# MCU.net
KiCad netlist of a schematic drawn in Altium Designer
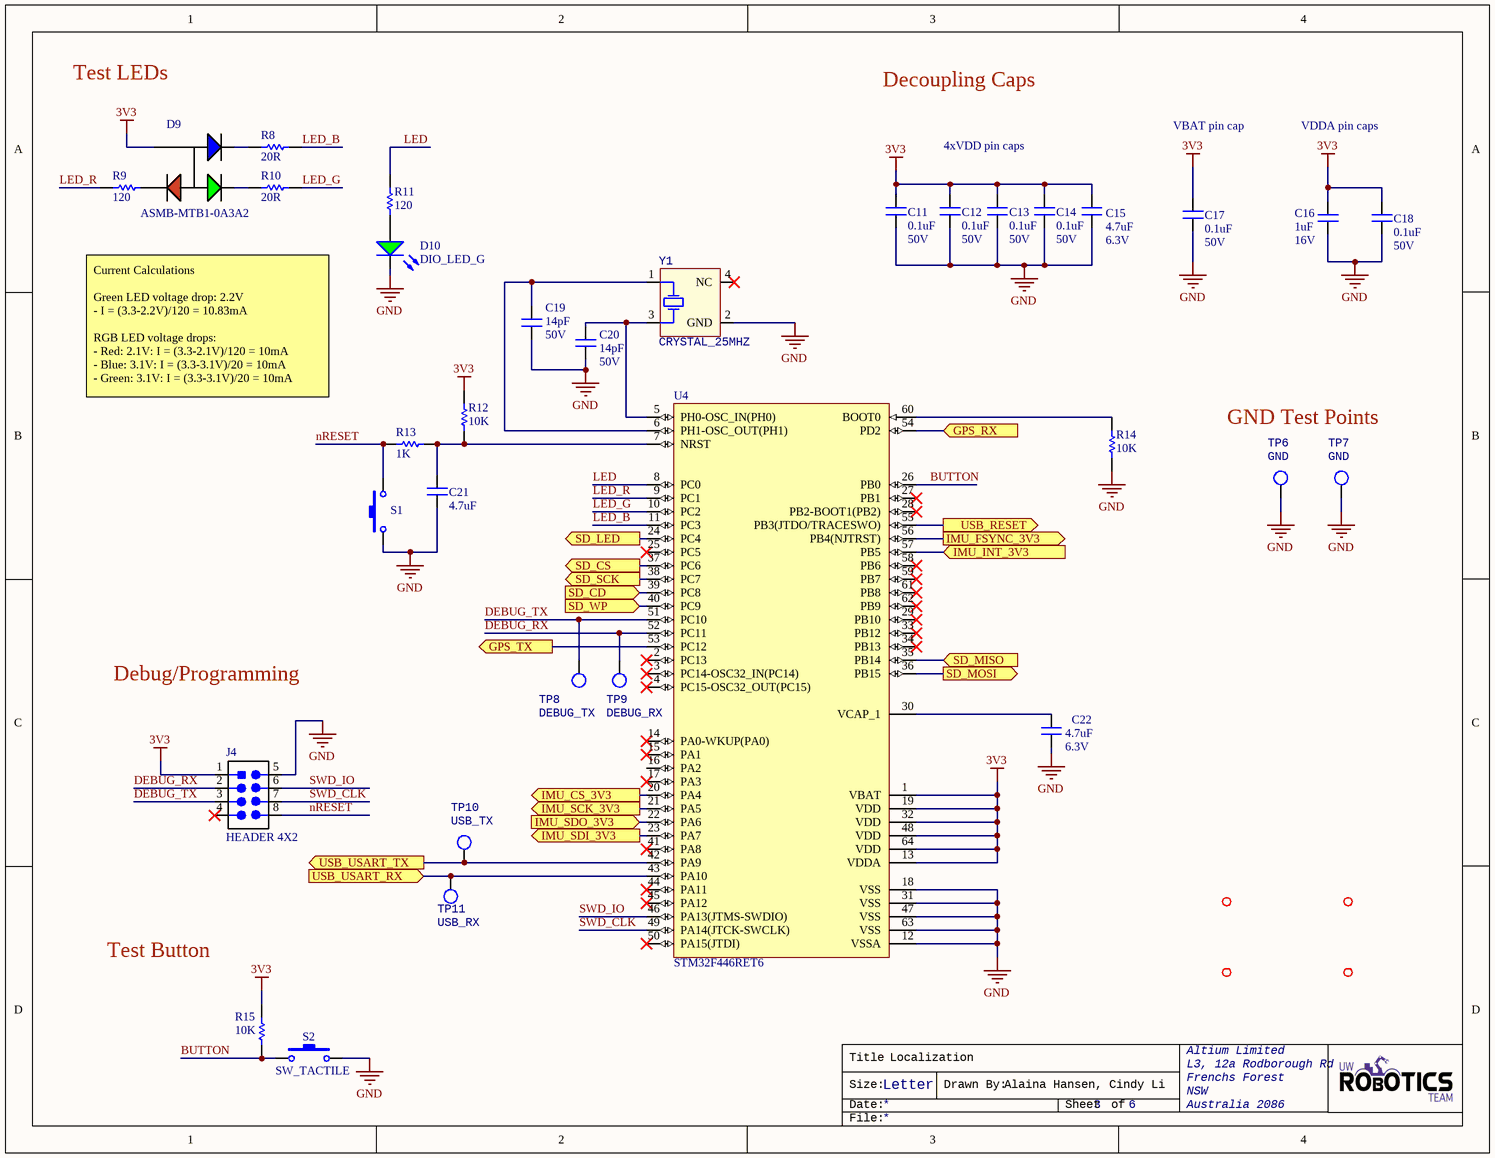
[diagram p0: MCU.SchDoc]

(export (version "E")
  (design (tool "Eeschema 10.0.6"))
  (components
    (comp (ref "C11")
      (value "0.1uF")
      (footprint "CAPC2012X140N")
      (description "CAP CER 0.1UF 50V X7R 0805")
      (fields
        (field (name "TOLERANCE") "10%")
        (field (name "VOLTAGE RATING") "50V")
        (field (name "Comment") "CAP_0.1uF_50V_0805")
      )
      (libsource (lib "UWRT_Schematic_Library_2020") (part "CAP_0.1uF_50V_0805"))
    )
    (comp (ref "C12")
      (value "0.1uF")
      (footprint "CAPC2012X140N")
      (description "CAP CER 0.1UF 50V X7R 0805")
      (fields
        (field (name "TOLERANCE") "10%")
        (field (name "VOLTAGE RATING") "50V")
        (field (name "Comment") "CAP_0.1uF_50V_0805")
      )
      (libsource (lib "UWRT_Schematic_Library_2020") (part "CAP_0.1uF_50V_0805"))
    )
    (comp (ref "C13")
      (value "0.1uF")
      (footprint "CAPC2012X140N")
      (description "CAP CER 0.1UF 50V X7R 0805")
      (fields
        (field (name "TOLERANCE") "10%")
        (field (name "VOLTAGE RATING") "50V")
        (field (name "Comment") "CAP_0.1uF_50V_0805")
      )
      (libsource (lib "UWRT_Schematic_Library_2020") (part "CAP_0.1uF_50V_0805"))
    )
    (comp (ref "C14")
      (value "0.1uF")
      (footprint "CAPC2012X140N")
      (description "CAP CER 0.1UF 50V X7R 0805")
      (fields
        (field (name "TOLERANCE") "10%")
        (field (name "VOLTAGE RATING") "50V")
        (field (name "Comment") "CAP_0.1uF_50V_0805")
      )
      (libsource (lib "UWRT_Schematic_Library_2020") (part "CAP_0.1uF_50V_0805"))
    )
    (comp (ref "C15")
      (value "4.7uF")
      (footprint "CAPC0603(1608)55_N")
      (description "CAP CER 4.7UF 6.3V X5R 0603")
      (fields (field (name "VOLTAGE RATING") "6.3V") (field (name "Comment") "CAP_4.7uF_0603"))
      (libsource (lib "UWRT_Schematic_Library_2020") (part "CAP_4.7uF_0603"))
    )
    (comp (ref "C16")
      (value "1uF")
      (footprint "CAPC0603(1608)55_N")
      (description "CAP CER 1UF 16V Y5V 0603")
      (fields
        (field (name "VOLTAGE RATING") "16V")
        (field (name "MANUFACTURER PART NUMBER") "CC0603ZRY5V7BB105")
        (field (name "Comment") "CAP_1uF_16V_0603")
      )
      (libsource (lib "UWRT_Schematic_Library_2020") (part "CAP_1uF_16V_0603"))
    )
    (comp (ref "C17")
      (value "0.1uF")
      (footprint "CAPC2012X140N")
      (description "CAP CER 0.1UF 50V X7R 0805")
      (fields
        (field (name "TOLERANCE") "10%")
        (field (name "VOLTAGE RATING") "50V")
        (field (name "Comment") "CAP_0.1uF_50V_0805")
      )
      (libsource (lib "UWRT_Schematic_Library_2020") (part "CAP_0.1uF_50V_0805"))
    )
    (comp (ref "C18")
      (value "0.1uF")
      (footprint "CAPC2012X140N")
      (description "CAP CER 0.1UF 50V X7R 0805")
      (fields
        (field (name "TOLERANCE") "10%")
        (field (name "VOLTAGE RATING") "50V")
        (field (name "Comment") "CAP_0.1uF_50V_0805")
      )
      (libsource (lib "UWRT_Schematic_Library_2020") (part "CAP_0.1uF_50V_0805"))
    )
    (comp (ref "C19")
      (value "14pF")
      (footprint "CAPC0603(1608)55_N")
      (description "Cap Ceramic 14pF 50V C0G 5% SMD 0603 125C Cardboard T/R")
      (fields
        (field (name "TOLERANCE") "5%")
        (field (name "VOLTAGE RATING (DC)") "50V")
        (field (name "Comment") "CL10C140JB8NNNC")
      )
      (libsource (lib "UWRT_Schematic_Library_2020") (part "CL10C140JB8NNNC"))
    )
    (comp (ref "C20")
      (value "14pF")
      (footprint "CAPC0603(1608)55_N")
      (description "Cap Ceramic 14pF 50V C0G 5% SMD 0603 125C Cardboard T/R")
      (fields
        (field (name "TOLERANCE") "5%")
        (field (name "VOLTAGE RATING (DC)") "50V")
        (field (name "Comment") "CL10C140JB8NNNC")
      )
      (libsource (lib "UWRT_Schematic_Library_2020") (part "CL10C140JB8NNNC"))
    )
    (comp (ref "C21")
      (value "4.7uF")
      (footprint "CAPC0603(1608)55_N")
      (description "CAP CER 4.7UF 6.3V X5R 0603")
      (fields (field (name "Comment") "CAP_4.7uF_0603"))
      (libsource (lib "UWRT_Schematic_Library_2020") (part "CAP_4.7uF_0603"))
    )
    (comp (ref "C22")
      (value "4.7uF")
      (footprint "CAPC0603(1608)55_N")
      (description "CAP CER 4.7UF 6.3V X5R 0603")
      (fields (field (name "VOLTAGE RATING") "6.3V") (field (name "Comment") "CAP_4.7uF_0603"))
      (libsource (lib "UWRT_Schematic_Library_2020") (part "CAP_4.7uF_0603"))
    )
    (comp (ref "D9")
      (value "LED_RGB")
      (footprint "LED_RGB")
      (description "LED RGB DIFFUSED 4PLCC SMD")
      (fields (field (name "MANUFACTURER PART NUMBER 1") "ASMB-MTB1-0A3A2"))
      (libsource (lib "UWRT_Schematic_Library_2020") (part "LED_RGB"))
    )
    (comp (ref "D10")
      (value "DIO_LED_G")
      (footprint "LED_0805_LINE")
      (description "LED GREEN DIFFUSED 0805 SMD")
      (libsource (lib "UWRT_Schematic_Library_2020") (part "DIO_LED_G"))
    )
    (comp (ref "J4")
      (value "HEADER 4X2")
      (footprint "UWRT_Footprint_Library_2020:HEADER_2X4")
      (description "CONN HEADER VERT 8POS 2.54MM")
      (libsource (lib "UWRT_Schematic_Library_2020") (part "HEADER 4X2"))
    )
    (comp (ref "MH1")
      (value "MOUNTING_HOLES")
      (footprint "MOUNTING_HOLE")
      (description "6cm x 6cm")
      (libsource (lib "UWRT_Schematic_Library_2020") (part "MOUNTING_HOLES"))
    )
    (comp (ref "MH2")
      (value "MOUNTING_HOLES")
      (footprint "MOUNTING_HOLE")
      (description "6cm x 6cm")
      (libsource (lib "UWRT_Schematic_Library_2020") (part "MOUNTING_HOLES"))
    )
    (comp (ref "MH3")
      (value "MOUNTING_HOLES")
      (footprint "MOUNTING_HOLE")
      (description "6cm x 6cm")
      (libsource (lib "UWRT_Schematic_Library_2020") (part "MOUNTING_HOLES"))
    )
    (comp (ref "MH4")
      (value "MOUNTING_HOLES")
      (footprint "MOUNTING_HOLE")
      (description "6cm x 6cm")
      (libsource (lib "UWRT_Schematic_Library_2020") (part "MOUNTING_HOLES"))
    )
    (comp (ref "R8")
      (value "20R")
      (footprint "RESC0603(1608)_N")
      (description "RES SMD 20 OHM 5% 1/10W 0603")
      (fields (field (name "TOLERANCE") "5%") (field (name "Comment") "RES_20R_0603"))
      (libsource (lib "UWRT_Schematic_Library_2020") (part "RES_20R_0603"))
    )
    (comp (ref "R9")
      (value "120")
      (footprint "RESC0603(1608)_N")
      (description "RES SMD 120 OHM 5% 1/10W 0603")
      (fields (field (name "TOLERANCE") "5%") (field (name "Comment") "RES_120R_0603"))
      (libsource (lib "UWRT_Schematic_Library_2020") (part "RES_120R_0603"))
    )
    (comp (ref "R10")
      (value "20R")
      (footprint "RESC0603(1608)_N")
      (description "RES SMD 20 OHM 5% 1/10W 0603")
      (fields (field (name "TOLERANCE") "5%") (field (name "Comment") "RES_20R_0603"))
      (libsource (lib "UWRT_Schematic_Library_2020") (part "RES_20R_0603"))
    )
    (comp (ref "R11")
      (value "120")
      (footprint "RESC0603(1608)_N")
      (description "RES SMD 120 OHM 5% 1/10W 0603")
      (fields (field (name "TOLERANCE") "5%") (field (name "Comment") "RES_120R_0603"))
      (libsource (lib "UWRT_Schematic_Library_2020") (part "RES_120R_0603"))
    )
    (comp (ref "R12")
      (value "10K")
      (footprint "RESC0603(1608)_N")
      (description "RES SMD 10K OHM 5% 1/10W 0603")
      (fields (field (name "TOLERANCE") "5%") (field (name "Comment") "RES_10K_0603"))
      (libsource (lib "UWRT_Schematic_Library_2020") (part "RES_10K_0603"))
    )
    (comp (ref "R13")
      (value "1K")
      (footprint "RESC0603(1608)_N")
      (description "RES SMD 1K OHM 5% 1/10W 0603")
      (fields (field (name "TOLERANCE") "5%") (field (name "Comment") "RES_1K_0603"))
      (libsource (lib "UWRT_Schematic_Library_2020") (part "RES_1K_0603"))
    )
    (comp (ref "R14")
      (value "10K")
      (footprint "RESC0603(1608)_N")
      (description "RES SMD 10K OHM 5% 1/10W 0603")
      (fields (field (name "TOLERANCE") "5%") (field (name "Comment") "RES_10K_0603"))
      (libsource (lib "UWRT_Schematic_Library_2020") (part "RES_10K_0603"))
    )
    (comp (ref "R15")
      (value "10K")
      (footprint "RESC0603(1608)_N")
      (description "RES SMD 10K OHM 5% 1/10W 0603")
      (fields (field (name "TOLERANCE") "5%") (field (name "Comment") "RES_10K_0603"))
      (libsource (lib "UWRT_Schematic_Library_2020") (part "RES_10K_0603"))
    )
    (comp (ref "S1")
      (value "SW_TACTILE")
      (footprint "B3U-1100P")
      (description "Tactile Switch (Grey)")
      (libsource (lib "UWRT_Schematic_Library_2020") (part "SW_TACTILE"))
    )
    (comp (ref "S2")
      (value "SW_TACTILE")
      (footprint "B3U-1100P")
      (description "Tactile Switch (Grey)")
      (libsource (lib "UWRT_Schematic_Library_2020") (part "SW_TACTILE"))
    )
    (comp (ref "TP6")
      (value "GND")
      (footprint "TESTPOINT_LOOP")
      (description "Loop testpoint through-hole pad")
      (libsource (lib "UWRT_Schematic_Library_2020") (part "TESTPOINT_LOOP"))
    )
    (comp (ref "TP7")
      (value "GND")
      (footprint "TESTPOINT_LOOP")
      (description "Loop testpoint through-hole pad")
      (libsource (lib "UWRT_Schematic_Library_2020") (part "TESTPOINT_LOOP"))
    )
    (comp (ref "TP8")
      (value "DEBUG_TX")
      (footprint "TESTPOINT_LOOP")
      (description "Loop testpoint through-hole pad")
      (libsource (lib "UWRT_Schematic_Library_2020") (part "TESTPOINT_LOOP"))
    )
    (comp (ref "TP9")
      (value "DEBUG_RX")
      (footprint "TESTPOINT_LOOP")
      (description "Loop testpoint through-hole pad")
      (libsource (lib "UWRT_Schematic_Library_2020") (part "TESTPOINT_LOOP"))
    )
    (comp (ref "TP10")
      (value "USB_TX")
      (footprint "TESTPOINT_LOOP")
      (description "Loop testpoint through-hole pad")
      (libsource (lib "UWRT_Schematic_Library_2020") (part "TESTPOINT_LOOP"))
    )
    (comp (ref "TP11")
      (value "USB_RX")
      (footprint "TESTPOINT_LOOP")
      (description "Loop testpoint through-hole pad")
      (libsource (lib "UWRT_Schematic_Library_2020") (part "TESTPOINT_LOOP"))
    )
    (comp (ref "U4")
      (value "STM32F446RET6")
      (footprint "STM-LQFP64_L")
      (libsource (lib "UWRT_Schematic_Library_2020") (part "MCU_STM32F446RET6"))
    )
    (comp (ref "Y1")
      (value "CRYSTAL_25MHZ")
      (footprint "SOIC254P1016X440-4N")
      (description "CRYSTAL 25.0000MHZ 12PF SMD")
      (libsource (lib "UWRT_Schematic_Library_2020") (part "CRYSTAL_25MHZ"))
    )
  )
  (nets
    (net (code "1") (name "/BUTTON") (class "Default")
      (node (ref "R15") (pin "2") (pinfunction "2_2") (pintype "passive"))
      (node (ref "S2") (pin "1") (pinfunction "1_1") (pintype "passive"))
      (node (ref "U4") (pin "26") (pinfunction "PB0_26") (pintype "bidirectional"))
    )
    (net (code "2") (name "/DEBUG_RX") (class "Default")
      (node (ref "J4") (pin "2") (pinfunction "2_2") (pintype "passive"))
      (node (ref "TP9") (pin "1") (pintype "passive"))
      (node (ref "U4") (pin "52") (pinfunction "PC11_52") (pintype "bidirectional"))
    )
    (net (code "3") (name "/DEBUG_TX") (class "Default")
      (node (ref "J4") (pin "3") (pinfunction "3_3") (pintype "passive"))
      (node (ref "TP8") (pin "1") (pintype "passive"))
      (node (ref "U4") (pin "51") (pinfunction "PC10_51") (pintype "bidirectional"))
    )
    (net (code "4") (name "/GPS_RX") (class "Default")
      (node (ref "U4") (pin "54") (pinfunction "PD2_54") (pintype "bidirectional"))
    )
    (net (code "5") (name "/GPS_TX") (class "Default")
      (node (ref "U4") (pin "53") (pinfunction "PC12_53") (pintype "bidirectional"))
    )
    (net (code "6") (name "/IMU_CS_3V3") (class "Default")
      (node (ref "U4") (pin "20") (pinfunction "PA4_20") (pintype "bidirectional"))
    )
    (net (code "7") (name "/IMU_FSYNC_3V3") (class "Default")
      (node (ref "U4") (pin "56") (pinfunction "PB4(NJTRST)_56") (pintype "bidirectional"))
    )
    (net (code "8") (name "/IMU_INT_3V3") (class "Default")
      (node (ref "U4") (pin "57") (pinfunction "PB5_57") (pintype "bidirectional"))
    )
    (net (code "9") (name "/IMU_SCK_3V3") (class "Default")
      (node (ref "U4") (pin "21") (pinfunction "PA5_21") (pintype "bidirectional"))
    )
    (net (code "10") (name "/IMU_SDI_3V3") (class "Default")
      (node (ref "U4") (pin "23") (pinfunction "PA7_23") (pintype "bidirectional"))
    )
    (net (code "11") (name "/IMU_SDO_3V3") (class "Default")
      (node (ref "U4") (pin "22") (pinfunction "PA6_22") (pintype "bidirectional"))
    )
    (net (code "12") (name "/LED") (class "Default")
      (node (ref "R11") (pin "1") (pinfunction "1_1") (pintype "passive"))
      (node (ref "U4") (pin "8") (pinfunction "PC0_8") (pintype "bidirectional"))
    )
    (net (code "13") (name "/LED_B") (class "Default")
      (node (ref "R8") (pin "2") (pinfunction "2_2") (pintype "passive"))
      (node (ref "U4") (pin "11") (pinfunction "PC3_11") (pintype "bidirectional"))
    )
    (net (code "14") (name "/LED_G") (class "Default")
      (node (ref "R10") (pin "2") (pinfunction "2_2") (pintype "passive"))
      (node (ref "U4") (pin "10") (pinfunction "PC2_10") (pintype "bidirectional"))
    )
    (net (code "15") (name "/LED_R") (class "Default")
      (node (ref "R9") (pin "1") (pinfunction "1_1") (pintype "passive"))
      (node (ref "U4") (pin "9") (pinfunction "PC1_9") (pintype "bidirectional"))
    )
    (net (code "16") (name "/SD_CD") (class "Default")
      (node (ref "U4") (pin "39") (pinfunction "PC8_39") (pintype "bidirectional"))
    )
    (net (code "17") (name "/SD_CS") (class "Default")
      (node (ref "U4") (pin "37") (pinfunction "PC6_37") (pintype "bidirectional"))
    )
    (net (code "18") (name "/SD_LED") (class "Default")
      (node (ref "U4") (pin "24") (pinfunction "PC4_24") (pintype "bidirectional"))
    )
    (net (code "19") (name "/SD_MISO") (class "Default")
      (node (ref "U4") (pin "35") (pinfunction "PB14_35") (pintype "bidirectional"))
    )
    (net (code "20") (name "/SD_MOSI") (class "Default")
      (node (ref "U4") (pin "36") (pinfunction "PB15_36") (pintype "bidirectional"))
    )
    (net (code "21") (name "/SD_SCK") (class "Default")
      (node (ref "U4") (pin "38") (pinfunction "PC7_38") (pintype "bidirectional"))
    )
    (net (code "22") (name "/SD_WP") (class "Default")
      (node (ref "U4") (pin "40") (pinfunction "PC9_40") (pintype "bidirectional"))
    )
    (net (code "23") (name "/SWD_CLK") (class "Default")
      (node (ref "J4") (pin "7") (pinfunction "3_7") (pintype "passive"))
      (node (ref "U4") (pin "49") (pinfunction "PA14(JTCK-SWCLK)_49") (pintype "bidirectional"))
    )
    (net (code "24") (name "/SWD_IO") (class "Default")
      (node (ref "J4") (pin "6") (pinfunction "2_6") (pintype "passive"))
      (node (ref "U4") (pin "46") (pinfunction "PA13(JTMS-SWDIO)_46") (pintype "bidirectional"))
    )
    (net (code "25") (name "/USB_RESET") (class "Default")
      (node (ref "U4") (pin "55") (pinfunction "PB3(JTDO/TRACESWO)_55") (pintype "bidirectional"))
    )
    (net (code "26") (name "/USB_USART_RX") (class "Default")
      (node (ref "TP11") (pin "1") (pintype "passive"))
      (node (ref "U4") (pin "43") (pinfunction "PA10_43") (pintype "bidirectional"))
    )
    (net (code "27") (name "/USB_USART_TX") (class "Default")
      (node (ref "TP10") (pin "1") (pintype "passive"))
      (node (ref "U4") (pin "42") (pinfunction "PA9_42") (pintype "bidirectional"))
    )
    (net (code "28") (name "/nRESET") (class "Default")
      (node (ref "J4") (pin "8") (pinfunction "4_8") (pintype "passive"))
      (node (ref "R13") (pin "1") (pinfunction "1_1") (pintype "passive"))
      (node (ref "S1") (pin "2") (pinfunction "2_2") (pintype "passive"))
    )
    (net (code "29") (name "3V3") (class "Default")
      (node (ref "C11") (pin "2") (pinfunction "2_2") (pintype "passive"))
      (node (ref "C12") (pin "2") (pinfunction "2_2") (pintype "passive"))
      (node (ref "C13") (pin "2") (pinfunction "2_2") (pintype "passive"))
      (node (ref "C14") (pin "2") (pinfunction "2_2") (pintype "passive"))
      (node (ref "C15") (pin "2") (pinfunction "2_2") (pintype "passive"))
      (node (ref "C16") (pin "2") (pinfunction "2_2") (pintype "passive"))
      (node (ref "C17") (pin "2") (pinfunction "2_2") (pintype "passive"))
      (node (ref "C18") (pin "2") (pinfunction "2_2") (pintype "passive"))
      (node (ref "D9") (pin "4") (pinfunction "9_4") (pintype "passive"))
      (node (ref "J4") (pin "1") (pinfunction "VCC_1") (pintype "passive"))
      (node (ref "R12") (pin "2") (pinfunction "2_2") (pintype "passive"))
      (node (ref "R15") (pin "1") (pinfunction "1_1") (pintype "passive"))
      (node (ref "U4") (pin "1") (pinfunction "VBAT_1") (pintype "power_in"))
      (node (ref "U4") (pin "13") (pinfunction "VDDA_13") (pintype "power_in"))
      (node (ref "U4") (pin "19") (pinfunction "VDD_19") (pintype "power_in"))
      (node (ref "U4") (pin "32") (pinfunction "VDD_32") (pintype "power_in"))
      (node (ref "U4") (pin "48") (pinfunction "VDD_48") (pintype "power_in"))
      (node (ref "U4") (pin "64") (pinfunction "VDD_64") (pintype "power_in"))
    )
    (net (code "30") (name "GND") (class "Default")
      (node (ref "C11") (pin "1") (pinfunction "1_1") (pintype "passive"))
      (node (ref "C12") (pin "1") (pinfunction "1_1") (pintype "passive"))
      (node (ref "C13") (pin "1") (pinfunction "1_1") (pintype "passive"))
      (node (ref "C14") (pin "1") (pinfunction "1_1") (pintype "passive"))
      (node (ref "C15") (pin "1") (pinfunction "1_1") (pintype "passive"))
      (node (ref "C16") (pin "1") (pinfunction "1_1") (pintype "passive"))
      (node (ref "C17") (pin "1") (pinfunction "1_1") (pintype "passive"))
      (node (ref "C18") (pin "1") (pinfunction "1_1") (pintype "passive"))
      (node (ref "C19") (pin "1") (pinfunction "1_1") (pintype "passive"))
      (node (ref "C20") (pin "1") (pinfunction "1_1") (pintype "passive"))
      (node (ref "C21") (pin "1") (pinfunction "1_1") (pintype "passive"))
      (node (ref "C22") (pin "1") (pinfunction "1_1") (pintype "passive"))
      (node (ref "D10") (pin "2") (pinfunction "K_2") (pintype "passive"))
      (node (ref "J4") (pin "5") (pinfunction "GND_5") (pintype "passive"))
      (node (ref "R14") (pin "2") (pinfunction "2_2") (pintype "passive"))
      (node (ref "S1") (pin "1") (pinfunction "1_1") (pintype "passive"))
      (node (ref "S2") (pin "2") (pinfunction "2_2") (pintype "passive"))
      (node (ref "TP6") (pin "1") (pintype "passive"))
      (node (ref "TP7") (pin "1") (pintype "passive"))
      (node (ref "U4") (pin "12") (pinfunction "VSSA_12") (pintype "power_in"))
      (node (ref "U4") (pin "18") (pinfunction "VSS_18") (pintype "power_in"))
      (node (ref "U4") (pin "31") (pinfunction "VSS_31") (pintype "power_in"))
      (node (ref "U4") (pin "47") (pinfunction "VSS_47") (pintype "power_in"))
      (node (ref "U4") (pin "63") (pinfunction "VSS_63") (pintype "power_in"))
      (node (ref "Y1") (pin "2") (pinfunction "GND_2") (pintype "power_in"))
    )
    (net (code "31") (name "Net-(D9-10)") (class "Default")
      (node (ref "D9") (pin "3") (pinfunction "10_3") (pintype "passive"))
      (node (ref "R8") (pin "1") (pinfunction "1_1") (pintype "passive"))
    )
    (net (code "32") (name "Net-(D9-11)") (class "Default")
      (node (ref "D9") (pin "1") (pinfunction "11_1") (pintype "passive"))
      (node (ref "R9") (pin "2") (pinfunction "2_2") (pintype "passive"))
    )
    (net (code "33") (name "Net-(D9-12)") (class "Default")
      (node (ref "D9") (pin "2") (pinfunction "12_2") (pintype "passive"))
      (node (ref "R10") (pin "1") (pinfunction "1_1") (pintype "passive"))
    )
    (net (code "34") (name "Net-(D10-A)") (class "Default")
      (node (ref "D10") (pin "1") (pinfunction "A_1") (pintype "passive"))
      (node (ref "R11") (pin "2") (pinfunction "2_2") (pintype "passive"))
    )
    (net (code "35") (name "Net-(U4-BOOT0)") (class "Default")
      (node (ref "R14") (pin "1") (pinfunction "1_1") (pintype "passive"))
      (node (ref "U4") (pin "60") (pinfunction "BOOT0_60") (pintype "input"))
    )
    (net (code "36") (name "Net-(U4-NRST)") (class "Default")
      (node (ref "C21") (pin "2") (pinfunction "2_2") (pintype "passive"))
      (node (ref "R12") (pin "1") (pinfunction "1_1") (pintype "passive"))
      (node (ref "R13") (pin "2") (pinfunction "2_2") (pintype "passive"))
      (node (ref "U4") (pin "7") (pinfunction "NRST_7") (pintype "bidirectional"))
    )
    (net (code "37") (name "Net-(U4-PH0-OSC_IN(PH0))") (class "Default")
      (node (ref "C20") (pin "2") (pinfunction "2_2") (pintype "passive"))
      (node (ref "U4") (pin "5") (pinfunction "PH0-OSC_IN(PH0)_5") (pintype "bidirectional"))
      (node (ref "Y1") (pin "3") (pinfunction "HOT_3") (pintype "passive"))
    )
    (net (code "38") (name "Net-(U4-PH1-OSC_OUT(PH1))") (class "Default")
      (node (ref "C19") (pin "2") (pinfunction "2_2") (pintype "passive"))
      (node (ref "U4") (pin "6") (pinfunction "PH1-OSC_OUT(PH1)_6") (pintype "bidirectional"))
      (node (ref "Y1") (pin "1") (pinfunction "HOT_1") (pintype "passive"))
    )
    (net (code "39") (name "Net-(U4-VCAP_1)") (class "Default")
      (node (ref "C22") (pin "2") (pinfunction "2_2") (pintype "passive"))
      (node (ref "U4") (pin "30") (pinfunction "VCAP_1_30") (pintype "passive"))
    )
    (net (code "40") (name "unconnected-(J4-Pad4)") (class "Default")
      (node (ref "J4") (pin "4") (pinfunction "4_4") (pintype "passive+no_connect"))
    )
    (net (code "41") (name "unconnected-(U4-PA0-WKUP(PA0)-Pad14)") (class "Default")
      (node (ref "U4") (pin "14") (pinfunction "PA0-WKUP(PA0)_14") (pintype "bidirectional+no_connect"))
    )
    (net (code "42") (name "unconnected-(U4-PA1-Pad15)") (class "Default")
      (node (ref "U4") (pin "15") (pinfunction "PA1_15") (pintype "bidirectional+no_connect"))
    )
    (net (code "43") (name "unconnected-(U4-PA2-Pad16)") (class "Default")
      (node (ref "U4") (pin "16") (pinfunction "PA2_16") (pintype "bidirectional"))
    )
    (net (code "44") (name "unconnected-(U4-PA3-Pad17)") (class "Default")
      (node (ref "U4") (pin "17") (pinfunction "PA3_17") (pintype "bidirectional+no_connect"))
    )
    (net (code "45") (name "unconnected-(U4-PA8-Pad41)") (class "Default")
      (node (ref "U4") (pin "41") (pinfunction "PA8_41") (pintype "bidirectional+no_connect"))
    )
    (net (code "46") (name "unconnected-(U4-PA11-Pad44)") (class "Default")
      (node (ref "U4") (pin "44") (pinfunction "PA11_44") (pintype "bidirectional+no_connect"))
    )
    (net (code "47") (name "unconnected-(U4-PA12-Pad45)") (class "Default")
      (node (ref "U4") (pin "45") (pinfunction "PA12_45") (pintype "bidirectional+no_connect"))
    )
    (net (code "48") (name "unconnected-(U4-PA15(JTDI)-Pad50)") (class "Default")
      (node (ref "U4") (pin "50") (pinfunction "PA15(JTDI)_50") (pintype "bidirectional+no_connect"))
    )
    (net (code "49") (name "unconnected-(U4-PB1-Pad27)") (class "Default")
      (node (ref "U4") (pin "27") (pinfunction "PB1_27") (pintype "bidirectional+no_connect"))
    )
    (net (code "50") (name "unconnected-(U4-PB2-BOOT1(PB2)-Pad28)") (class "Default")
      (node (ref "U4") (pin "28") (pinfunction "PB2-BOOT1(PB2)_28") (pintype "bidirectional+no_connect"))
    )
    (net (code "51") (name "unconnected-(U4-PB6-Pad58)") (class "Default")
      (node (ref "U4") (pin "58") (pinfunction "PB6_58") (pintype "bidirectional+no_connect"))
    )
    (net (code "52") (name "unconnected-(U4-PB7-Pad59)") (class "Default")
      (node (ref "U4") (pin "59") (pinfunction "PB7_59") (pintype "bidirectional+no_connect"))
    )
    (net (code "53") (name "unconnected-(U4-PB8-Pad61)") (class "Default")
      (node (ref "U4") (pin "61") (pinfunction "PB8_61") (pintype "bidirectional+no_connect"))
    )
    (net (code "54") (name "unconnected-(U4-PB9-Pad62)") (class "Default")
      (node (ref "U4") (pin "62") (pinfunction "PB9_62") (pintype "bidirectional+no_connect"))
    )
    (net (code "55") (name "unconnected-(U4-PB10-Pad29)") (class "Default")
      (node (ref "U4") (pin "29") (pinfunction "PB10_29") (pintype "bidirectional+no_connect"))
    )
    (net (code "56") (name "unconnected-(U4-PB12-Pad33)") (class "Default")
      (node (ref "U4") (pin "33") (pinfunction "PB12_33") (pintype "bidirectional+no_connect"))
    )
    (net (code "57") (name "unconnected-(U4-PB13-Pad34)") (class "Default")
      (node (ref "U4") (pin "34") (pinfunction "PB13_34") (pintype "bidirectional+no_connect"))
    )
    (net (code "58") (name "unconnected-(U4-PC5-Pad25)") (class "Default")
      (node (ref "U4") (pin "25") (pinfunction "PC5_25") (pintype "bidirectional+no_connect"))
    )
    (net (code "59") (name "unconnected-(U4-PC13-Pad2)") (class "Default")
      (node (ref "U4") (pin "2") (pinfunction "PC13_2") (pintype "bidirectional+no_connect"))
    )
    (net (code "60") (name "unconnected-(U4-PC14-OSC32_IN(PC14)-Pad3)") (class "Default")
      (node (ref "U4") (pin "3") (pinfunction "PC14-OSC32_IN(PC14)_3") (pintype "bidirectional+no_connect"))
    )
    (net (code "61") (name "unconnected-(U4-PC15-OSC32_OUT(PC15)-Pad4)") (class "Default")
      (node (ref "U4") (pin "4") (pinfunction "PC15-OSC32_OUT(PC15)_4") (pintype "bidirectional+no_connect"))
    )
    (net (code "62") (name "unconnected-(Y1-NC-Pad4)") (class "Default")
      (node (ref "Y1") (pin "4") (pinfunction "NC_4") (pintype "passive+no_connect"))
    )
  )
)
